# mach_nguon_5V.net
KiCad netlist of a schematic drawn in Altium Designer
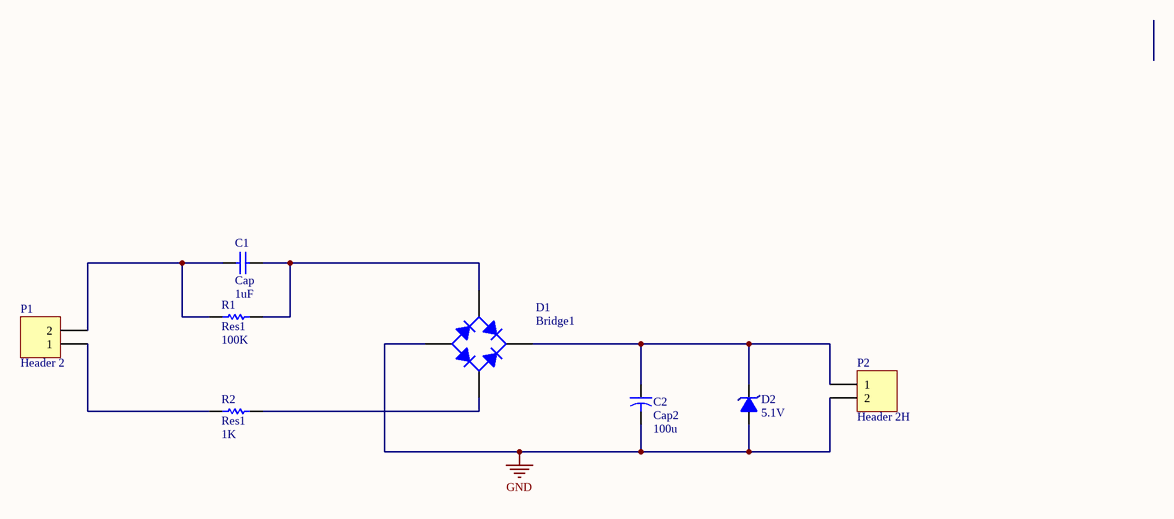
[diagram p0: mach nguon 5V.SchDoc]

(export (version "E")
  (design (tool "Eeschema 10.0.6"))
  (components
    (comp (ref "C1")
      (value "Cap")
      (footprint "RAD-0.3")
      (description "Capacitor")
      (fields (field (name "ALTIUM_VALUE") "1uF") (field (name "PUBLISHER") "Altium Limited"))
      (libsource (lib "Miscellaneous Devices") (part "Cap"))
    )
    (comp (ref "C2")
      (value "Cap2")
      (footprint "CAPR5-4X5")
      (description "Capacitor")
      (fields (field (name "ALTIUM_VALUE") "100u") (field (name "PUBLISHER") "Altium Limited"))
      (libsource (lib "Miscellaneous Devices") (part "Cap2"))
    )
    (comp (ref "D1")
      (value "Bridge1")
      (footprint "D-38")
      (description "Full Wave Diode Bridge")
      (fields (field (name "PUBLISHER") "Altium Limited"))
      (libsource (lib "Miscellaneous Devices") (part "Bridge1"))
    )
    (comp (ref "D2")
      (value "5.1V")
      (footprint "DIODE ZENNER SMD SOD80")
      (description "Dán")
      (libsource (lib "Altium_Lib_by_KhueNguyenCreator") (part "Diode Zener 5.1V"))
    )
    (comp (ref "P1")
      (value "Header 2")
      (footprint "HDR1X2")
      (description "Header, 2-Pin")
      (fields (field (name "PUBLISHER") "Altium Limited"))
      (libsource (lib "Miscellaneous Connectors") (part "Header 2"))
    )
    (comp (ref "P2")
      (value "Header 2H")
      (footprint "HDR1X2H")
      (description "Header, 2-Pin, Right Angle")
      (fields (field (name "PUBLISHER") "Altium Limited"))
      (libsource (lib "Miscellaneous Connectors") (part "Header 2H"))
    )
    (comp (ref "R1")
      (value "Res1")
      (footprint "AXIAL-0.3")
      (description "Resistor")
      (fields (field (name "ALTIUM_VALUE") "100K") (field (name "PUBLISHER") "Altium Limited"))
      (libsource (lib "Miscellaneous Devices") (part "Res1"))
    )
    (comp (ref "R2")
      (value "Res1")
      (footprint "AXIAL-0.3")
      (description "Resistor")
      (fields (field (name "ALTIUM_VALUE") "1K") (field (name "PUBLISHER") "Altium Limited"))
      (libsource (lib "Miscellaneous Devices") (part "Res1"))
    )
  )
  (nets
    (net (code "1") (name "GND") (class "Default")
      (node (ref "C2") (pin "2") (pinfunction "2_2") (pintype "passive"))
      (node (ref "D1") (pin "3") (pinfunction "A_3") (pintype "passive"))
      (node (ref "D2") (pin "1") (pinfunction "A_1") (pintype "passive"))
      (node (ref "P2") (pin "2") (pinfunction "2_2") (pintype "passive"))
    )
    (net (code "2") (name "Net-(C1-Pad1)") (class "Default")
      (node (ref "C1") (pin "1") (pinfunction "1_1") (pintype "passive"))
      (node (ref "P1") (pin "2") (pinfunction "2_2") (pintype "passive"))
      (node (ref "R1") (pin "1") (pinfunction "1_1") (pintype "passive"))
    )
    (net (code "3") (name "Net-(C1-Pad2)") (class "Default")
      (node (ref "C1") (pin "2") (pinfunction "2_2") (pintype "passive"))
      (node (ref "D1") (pin "4") (pinfunction "C_4") (pintype "passive"))
      (node (ref "R1") (pin "2") (pinfunction "2_2") (pintype "passive"))
    )
    (net (code "4") (name "Net-(D1-C-Pad2)") (class "Default")
      (node (ref "D1") (pin "2") (pinfunction "C_2") (pintype "passive"))
      (node (ref "R2") (pin "2") (pinfunction "2_2") (pintype "passive"))
    )
    (net (code "5") (name "Net-(D1-K)") (class "Default")
      (node (ref "C2") (pin "1") (pinfunction "1_1") (pintype "passive"))
      (node (ref "D1") (pin "1") (pinfunction "K_1") (pintype "passive"))
      (node (ref "D2") (pin "2") (pinfunction "K_2") (pintype "passive"))
      (node (ref "P2") (pin "1") (pinfunction "1_1") (pintype "passive"))
    )
    (net (code "6") (name "Net-(P1-Pad1)") (class "Default")
      (node (ref "P1") (pin "1") (pinfunction "1_1") (pintype "passive"))
      (node (ref "R2") (pin "1") (pinfunction "1_1") (pintype "passive"))
    )
  )
)
